# OK1050-C_V1_2_Lcd.net
KiCad netlist of a schematic drawn in Altium Designer
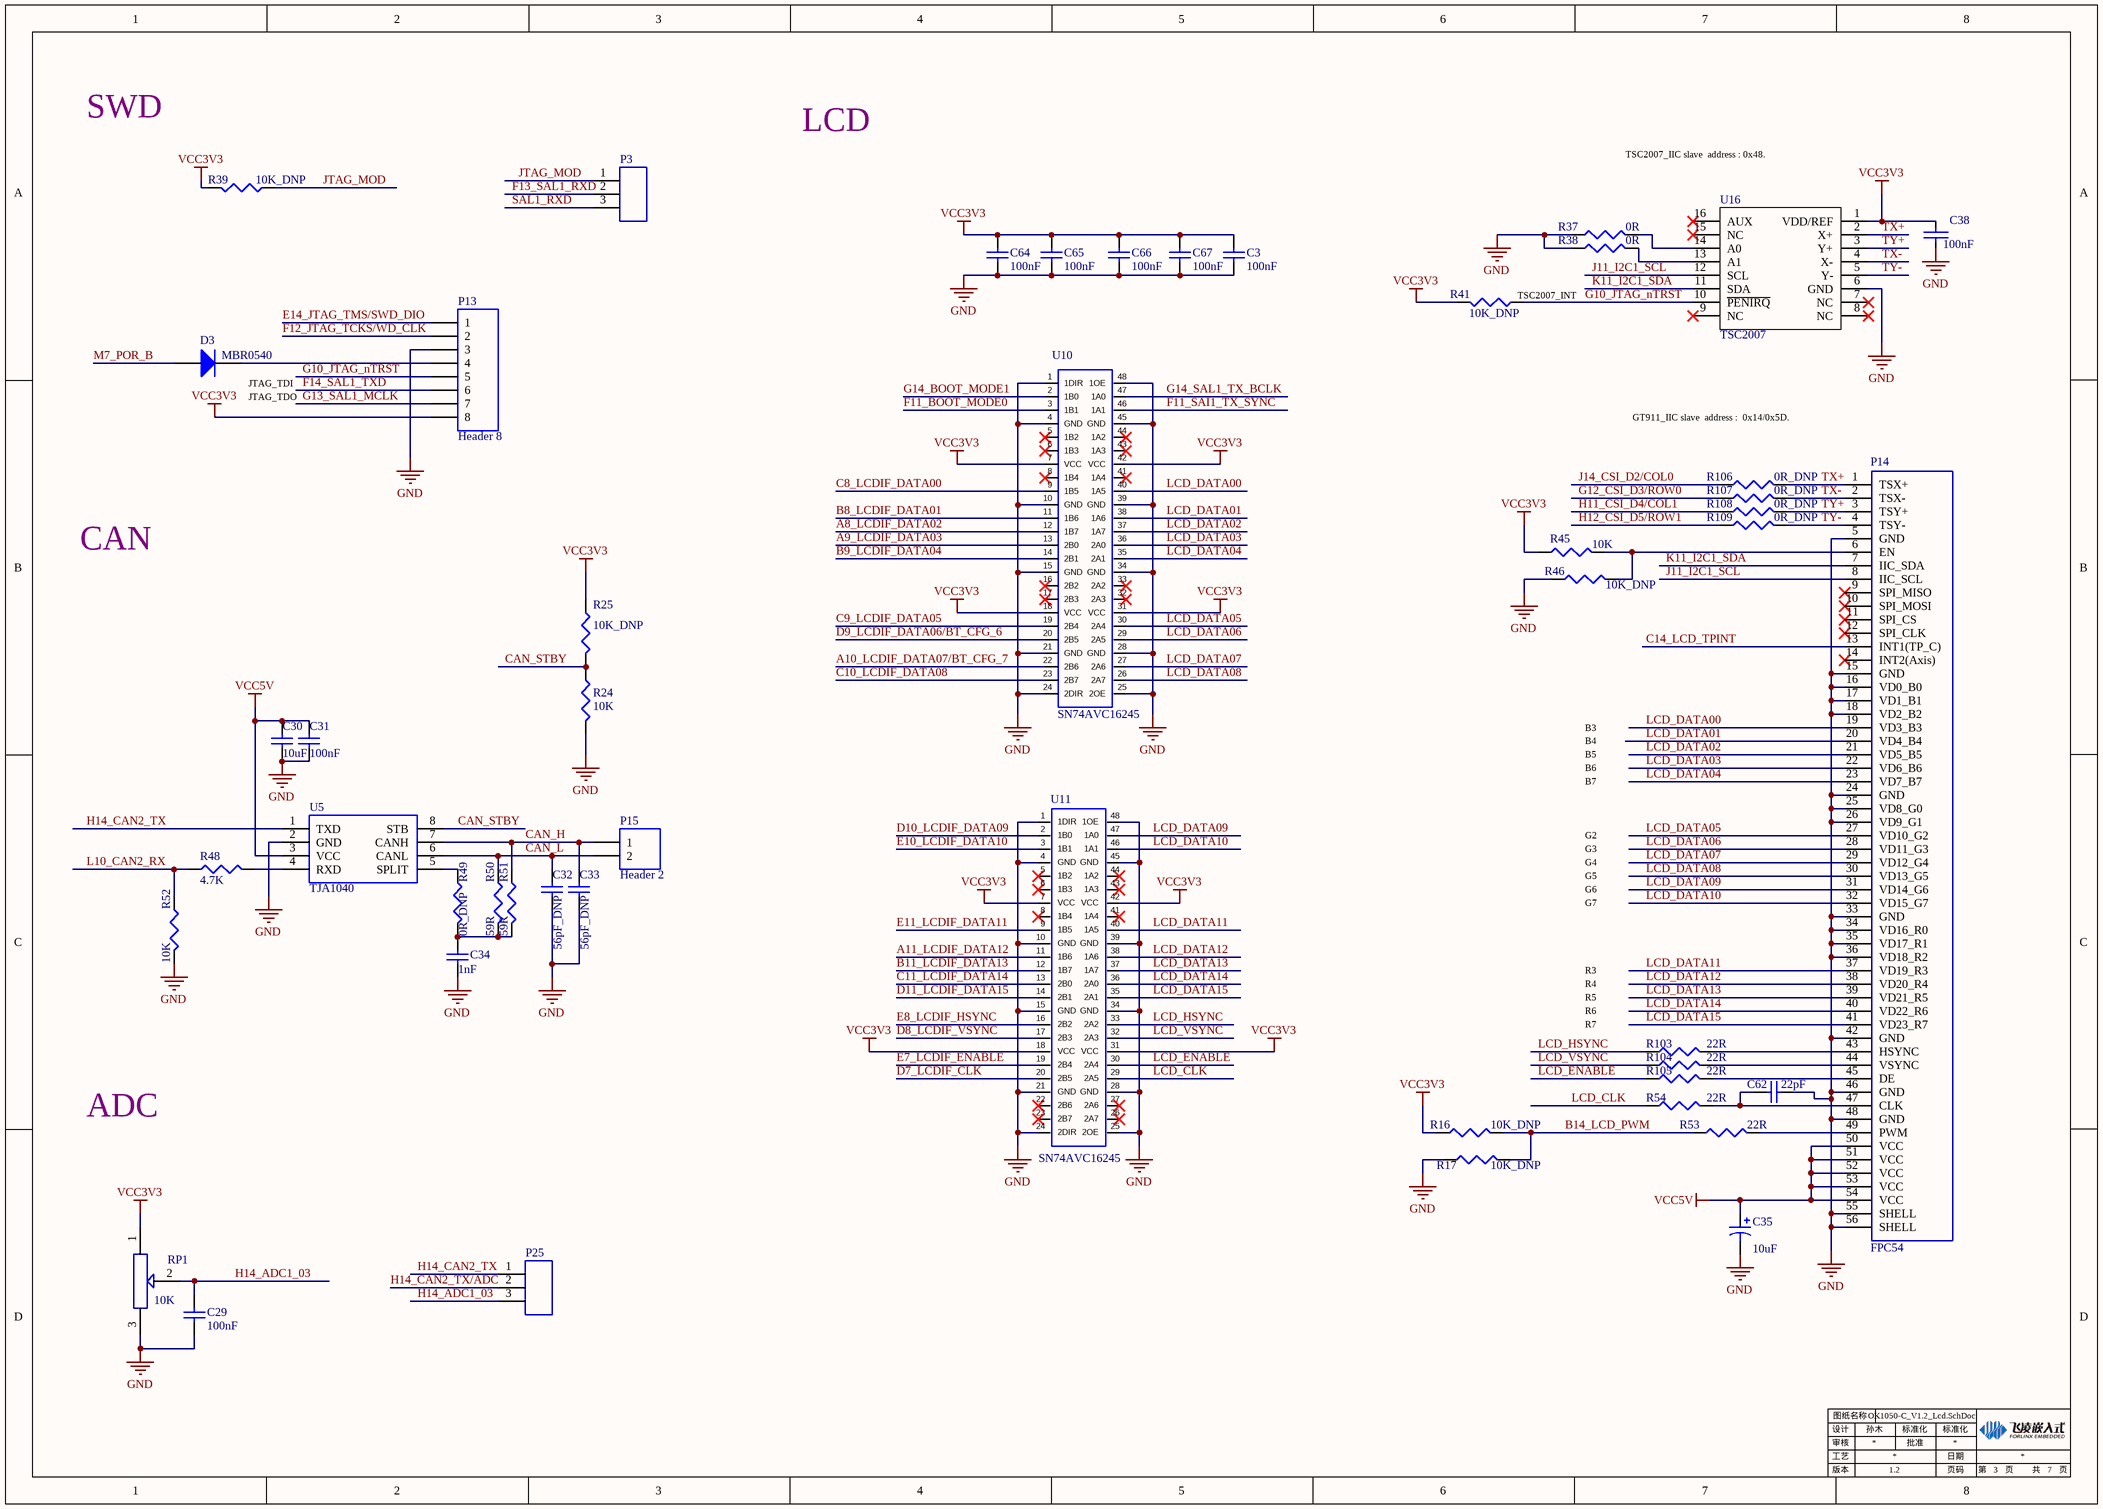
[diagram p0: OK1050-C_V1.2_Lcd.SchDoc]

(export (version "E")
  (design (tool "Eeschema 10.0.6"))
  (components
    (comp (ref "C3")
      (value "100nF")
      (footprint "0603C+")
      (description "Capacitor")
      (fields (field (name "PUBLISHER") "Altium Limited"))
      (libsource (lib "Miscellaneous Devices") (part "Cap"))
    )
    (comp (ref "C29")
      (value "100nF")
      (footprint "0603C+")
      (description "Capacitor")
      (fields (field (name "PUBLISHER") "Altium Limited"))
      (libsource (lib "Miscellaneous Devices") (part "Cap"))
    )
    (comp (ref "C30")
      (value "10uF")
      (footprint "0603C+")
      (description "Capacitor")
      (fields (field (name "PUBLISHER") "Altium Limited"))
      (libsource (lib "Miscellaneous Devices") (part "Cap"))
    )
    (comp (ref "C31")
      (value "100nF")
      (footprint "0603C+")
      (description "Capacitor")
      (fields (field (name "PUBLISHER") "Altium Limited"))
      (libsource (lib "Miscellaneous Devices") (part "Cap"))
    )
    (comp (ref "C32")
      (value "56pF_DNP")
      (footprint "0603C+")
      (description "Capacitor")
      (fields (field (name "PUBLISHER") "Altium Limited"))
      (libsource (lib "Miscellaneous Devices") (part "Cap"))
    )
    (comp (ref "C33")
      (value "56pF_DNP")
      (footprint "0603C+")
      (description "Capacitor")
      (fields (field (name "PUBLISHER") "Altium Limited"))
      (libsource (lib "Miscellaneous Devices") (part "Cap"))
    )
    (comp (ref "C34")
      (value "1nF")
      (footprint "0603C+")
      (description "Capacitor")
      (fields (field (name "PUBLISHER") "Altium Limited"))
      (libsource (lib "Miscellaneous Devices") (part "Cap"))
    )
    (comp (ref "C35")
      (value "10uF")
      (footprint "TC3216A")
      (description "Polarized Capacitor (Radial)")
      (fields (field (name "PUBLISHER") "Altium Limited"))
      (libsource (lib "Miscellaneous Devices") (part "Cap Pol1"))
    )
    (comp (ref "C38")
      (value "100nF")
      (footprint "0603C+")
      (libsource (lib "SMARTCORTEX M3-1700_1") (part "CAP_1"))
    )
    (comp (ref "C62")
      (value "22pF")
      (footprint "0603C+")
      (description "Capacitor")
      (fields (field (name "PUBLISHER") "Altium Limited"))
      (libsource (lib "Miscellaneous Devices") (part "Cap"))
    )
    (comp (ref "C64")
      (value "100nF")
      (footprint "0603C+")
      (description "Capacitor")
      (fields (field (name "PUBLISHER") "Altium Limited"))
      (libsource (lib "Miscellaneous Devices") (part "Cap"))
    )
    (comp (ref "C65")
      (value "100nF")
      (footprint "0603C+")
      (description "Capacitor")
      (fields (field (name "PUBLISHER") "Altium Limited"))
      (libsource (lib "Miscellaneous Devices") (part "Cap"))
    )
    (comp (ref "C66")
      (value "100nF")
      (footprint "0603C+")
      (description "Capacitor")
      (fields (field (name "PUBLISHER") "Altium Limited"))
      (libsource (lib "Miscellaneous Devices") (part "Cap"))
    )
    (comp (ref "C67")
      (value "100nF")
      (footprint "0603C+")
      (description "Capacitor")
      (fields (field (name "PUBLISHER") "Altium Limited"))
      (libsource (lib "Miscellaneous Devices") (part "Cap"))
    )
    (comp (ref "D3")
      (value "MBR0540")
      (footprint "Diode1.6*2.6")
      (description "Default Diode")
      (fields (field (name "PUBLISHER") "Altium Limited"))
      (libsource (lib "Miscellaneous Devices") (part "Diode"))
    )
    (comp (ref "P3") (value "P25") (footprint "HDR1X3") (libsource (lib "PCB_RT1052") (part "CON3")))
    (comp (ref "P13")
      (value "Header 8")
      (footprint "HDR1X8")
      (description "Header, 8-Pin")
      (fields (field (name "PUBLISHER") "Altium Limited"))
      (libsource (lib "PCB_RT1052_1") (part "Header 8"))
    )
    (comp (ref "P14") (value "FPC54") (footprint "FPC54") (libsource (lib "MyLIB") (part "FPC54")))
    (comp (ref "P15")
      (value "Header 2")
      (footprint "DG128-2P")
      (libsource (lib "PCB_RT1052") (part "Header 2"))
    )
    (comp (ref "P25") (value "P25") (footprint "HDR1X3") (libsource (lib "PCB_RT1052") (part "CON3")))
    (comp (ref "R16")
      (value "10K_DNP")
      (footprint "0603R+")
      (description "Resistor")
      (fields (field (name "PUBLISHER") "Altium Limited"))
      (libsource (lib "") (part "Res3_1"))
    )
    (comp (ref "R17")
      (value "10K_DNP")
      (footprint "0603R+")
      (description "Resistor")
      (fields (field (name "PUBLISHER") "Altium Limited"))
      (libsource (lib "") (part "Res3_1"))
    )
    (comp (ref "R24")
      (value "10K")
      (footprint "0603R+")
      (description "Resistor")
      (fields (field (name "PUBLISHER") "Altium Limited"))
      (libsource (lib "Miscellaneous Devices") (part "Res3"))
    )
    (comp (ref "R25")
      (value "10K_DNP")
      (footprint "0603R+")
      (description "Resistor")
      (fields (field (name "PUBLISHER") "Altium Limited"))
      (libsource (lib "Miscellaneous Devices") (part "Res3"))
    )
    (comp (ref "R37")
      (value "0R")
      (footprint "0603R+")
      (description "Resistor")
      (fields (field (name "PUBLISHER") "Altium Limited"))
      (libsource (lib "Sch") (part "Res3"))
    )
    (comp (ref "R38")
      (value "0R")
      (footprint "0603R+")
      (description "Resistor")
      (fields (field (name "PUBLISHER") "Altium Limited"))
      (libsource (lib "Sch") (part "Res3"))
    )
    (comp (ref "R39")
      (value "10K_DNP")
      (footprint "0603R+")
      (description "Resistor")
      (fields (field (name "PUBLISHER") "Altium Limited"))
      (libsource (lib "") (part "Res3_1"))
    )
    (comp (ref "R41")
      (value "10K_DNP")
      (footprint "0603R+")
      (description "Resistor")
      (fields (field (name "PUBLISHER") "Altium Limited"))
      (libsource (lib "Sch") (part "Res3"))
    )
    (comp (ref "R45")
      (value "10K")
      (footprint "0603R+")
      (description "Resistor")
      (fields (field (name "PUBLISHER") "Altium Limited"))
      (libsource (lib "") (part "Res3_1"))
    )
    (comp (ref "R46")
      (value "10K_DNP")
      (footprint "0603R+")
      (description "Resistor")
      (fields (field (name "PUBLISHER") "Altium Limited"))
      (libsource (lib "") (part "Res3_1"))
    )
    (comp (ref "R48")
      (value "4.7K")
      (footprint "0603R+")
      (description "Resistor")
      (fields (field (name "PUBLISHER") "Altium Limited"))
      (libsource (lib "Miscellaneous Devices") (part "Res3"))
    )
    (comp (ref "R49")
      (value "0R_DNP")
      (footprint "0603R+")
      (description "Resistor")
      (fields (field (name "PUBLISHER") "Altium Limited"))
      (libsource (lib "Miscellaneous Devices") (part "Res3"))
    )
    (comp (ref "R50")
      (value "59R")
      (footprint "0603R+")
      (description "Resistor")
      (fields (field (name "PUBLISHER") "Altium Limited"))
      (libsource (lib "Miscellaneous Devices") (part "Res3"))
    )
    (comp (ref "R51")
      (value "59R")
      (footprint "0603R+")
      (description "Resistor")
      (fields (field (name "PUBLISHER") "Altium Limited"))
      (libsource (lib "Miscellaneous Devices") (part "Res3"))
    )
    (comp (ref "R52")
      (value "10K")
      (footprint "0603R+")
      (description "Resistor")
      (fields (field (name "PUBLISHER") "Altium Limited"))
      (libsource (lib "Miscellaneous Devices") (part "Res3"))
    )
    (comp (ref "R53")
      (value "22R")
      (footprint "0603R+")
      (description "Resistor")
      (fields (field (name "PUBLISHER") "Altium Limited"))
      (libsource (lib "") (part "Res3_1"))
    )
    (comp (ref "R54")
      (value "22R")
      (footprint "0603R+")
      (description "Resistor")
      (fields (field (name "PUBLISHER") "Altium Limited"))
      (libsource (lib "") (part "Res3_1"))
    )
    (comp (ref "R103")
      (value "22R")
      (footprint "0603R+")
      (description "Resistor")
      (fields (field (name "PUBLISHER") "Altium Limited"))
      (libsource (lib "") (part "Res3_1"))
    )
    (comp (ref "R104")
      (value "22R")
      (footprint "0603R+")
      (description "Resistor")
      (fields (field (name "PUBLISHER") "Altium Limited"))
      (libsource (lib "") (part "Res3_1"))
    )
    (comp (ref "R105")
      (value "22R")
      (footprint "0603R+")
      (description "Resistor")
      (fields (field (name "PUBLISHER") "Altium Limited"))
      (libsource (lib "") (part "Res3_1"))
    )
    (comp (ref "R106")
      (value "0R_DNP")
      (footprint "0603R+")
      (description "Resistor")
      (fields (field (name "PUBLISHER") "Altium Limited"))
      (libsource (lib "Sch") (part "Res3"))
    )
    (comp (ref "R107")
      (value "0R_DNP")
      (footprint "0603R+")
      (description "Resistor")
      (fields (field (name "PUBLISHER") "Altium Limited"))
      (libsource (lib "Sch") (part "Res3"))
    )
    (comp (ref "R108")
      (value "0R_DNP")
      (footprint "0603R+")
      (description "Resistor")
      (fields (field (name "PUBLISHER") "Altium Limited"))
      (libsource (lib "Sch") (part "Res3"))
    )
    (comp (ref "R109")
      (value "0R_DNP")
      (footprint "0603R+")
      (description "Resistor")
      (fields (field (name "PUBLISHER") "Altium Limited"))
      (libsource (lib "Sch") (part "Res3"))
    )
    (comp (ref "RP1")
      (value "10K")
      (footprint "3296W")
      (fields (field (name "Comment") "VR-3296W"))
      (libsource (lib "Sch") (part "VR"))
    )
    (comp (ref "U5")
      (value "TJA1040")
      (footprint "SOP127P600X175-8N")
      (libsource (lib "IMX6QP") (part "TJA1040"))
    )
    (comp (ref "U10")
      (value "SN74AVC16245")
      (footprint "SN74VC16245")
      (libsource (lib "MyLIB") (part "SN74AVC16245"))
    )
    (comp (ref "U11")
      (value "SN74AVC16245")
      (footprint "SN74VC16245")
      (libsource (lib "MyLIB") (part "SN74AVC16245"))
    )
    (comp (ref "U16") (value "TSC2007") (footprint "TSC2007") (libsource (lib "IMX6Q-S3") (part "TSC2007")))
  )
  (nets
    (net (code "1") (name "/A8_LCDIF_DATA02") (class "Default")
      (node (ref "U10") (pin "12") (pinfunction "1B7_12") (pintype "passive"))
    )
    (net (code "2") (name "/A9_LCDIF_DATA03") (class "Default")
      (node (ref "U10") (pin "13") (pinfunction "2B0_13") (pintype "passive"))
    )
    (net (code "3") (name "/A10_LCDIF_DATA07{slash}BT_CFG_7") (class "Default")
      (node (ref "U10") (pin "22") (pinfunction "2B6_22") (pintype "passive"))
    )
    (net (code "4") (name "/A11_LCDIF_DATA12") (class "Default")
      (node (ref "U11") (pin "11") (pinfunction "1B6_11") (pintype "passive"))
    )
    (net (code "5") (name "/B8_LCDIF_DATA01") (class "Default")
      (node (ref "U10") (pin "11") (pinfunction "1B6_11") (pintype "passive"))
    )
    (net (code "6") (name "/B9_LCDIF_DATA04") (class "Default")
      (node (ref "U10") (pin "14") (pinfunction "2B1_14") (pintype "passive"))
    )
    (net (code "7") (name "/B11_LCDIF_DATA13") (class "Default")
      (node (ref "U11") (pin "12") (pinfunction "1B7_12") (pintype "passive"))
    )
    (net (code "8") (name "/B14_LCD_PWM") (class "Default")
      (node (ref "R16") (pin "2") (pinfunction "2_2") (pintype "passive"))
      (node (ref "R17") (pin "2") (pinfunction "2_2") (pintype "passive"))
      (node (ref "R53") (pin "1") (pinfunction "1_1") (pintype "passive"))
    )
    (net (code "9") (name "/C8_LCDIF_DATA00") (class "Default")
      (node (ref "U10") (pin "9") (pinfunction "1B5_9") (pintype "passive"))
    )
    (net (code "10") (name "/C9_LCDIF_DATA05") (class "Default")
      (node (ref "U10") (pin "19") (pinfunction "2B4_19") (pintype "passive"))
    )
    (net (code "11") (name "/C10_LCDIF_DATA08") (class "Default")
      (node (ref "U10") (pin "23") (pinfunction "2B7_23") (pintype "passive"))
    )
    (net (code "12") (name "/C11_LCDIF_DATA14") (class "Default")
      (node (ref "U11") (pin "13") (pinfunction "2B0_13") (pintype "passive"))
    )
    (net (code "13") (name "/C14_LCD_TPINT") (class "Default")
      (node (ref "P14") (pin "13") (pinfunction "INT1(TP_C)_13") (pintype "passive"))
    )
    (net (code "14") (name "/CAN_H") (class "Default")
      (node (ref "C33") (pin "1") (pinfunction "1_1") (pintype "passive"))
      (node (ref "P15") (pin "1") (pinfunction "1_1") (pintype "passive"))
      (node (ref "R51") (pin "1") (pinfunction "1_1") (pintype "passive"))
      (node (ref "U5") (pin "7") (pinfunction "CANH_7") (pintype "passive"))
    )
    (net (code "15") (name "/CAN_L") (class "Default")
      (node (ref "C32") (pin "1") (pinfunction "1_1") (pintype "passive"))
      (node (ref "P15") (pin "2") (pinfunction "2_2") (pintype "passive"))
      (node (ref "R50") (pin "1") (pinfunction "1_1") (pintype "passive"))
      (node (ref "U5") (pin "6") (pinfunction "CANL_6") (pintype "passive"))
    )
    (net (code "16") (name "/CAN_STBY") (class "Default")
      (node (ref "R24") (pin "1") (pinfunction "1_1") (pintype "passive"))
      (node (ref "R25") (pin "2") (pinfunction "2_2") (pintype "passive"))
      (node (ref "U5") (pin "8") (pinfunction "STB_8") (pintype "passive"))
    )
    (net (code "17") (name "/D7_LCDIF_CLK") (class "Default")
      (node (ref "U11") (pin "20") (pinfunction "2B5_20") (pintype "passive"))
    )
    (net (code "18") (name "/D8_LCDIF_VSYNC") (class "Default")
      (node (ref "U11") (pin "17") (pinfunction "2B3_17") (pintype "passive"))
    )
    (net (code "19") (name "/D9_LCDIF_DATA06{slash}BT_CFG_6") (class "Default")
      (node (ref "U10") (pin "20") (pinfunction "2B5_20") (pintype "passive"))
    )
    (net (code "20") (name "/D10_LCDIF_DATA09") (class "Default")
      (node (ref "U11") (pin "2") (pinfunction "1B0_2") (pintype "passive"))
    )
    (net (code "21") (name "/D11_LCDIF_DATA15") (class "Default")
      (node (ref "U11") (pin "14") (pinfunction "2B1_14") (pintype "passive"))
    )
    (net (code "22") (name "/E7_LCDIF_ENABLE") (class "Default")
      (node (ref "U11") (pin "19") (pinfunction "2B4_19") (pintype "passive"))
    )
    (net (code "23") (name "/E8_LCDIF_HSYNC") (class "Default")
      (node (ref "U11") (pin "16") (pinfunction "2B2_16") (pintype "passive"))
    )
    (net (code "24") (name "/E10_LCDIF_DATA10") (class "Default")
      (node (ref "U11") (pin "3") (pinfunction "1B1_3") (pintype "passive"))
    )
    (net (code "25") (name "/E11_LCDIF_DATA11") (class "Default")
      (node (ref "U11") (pin "9") (pinfunction "1B5_9") (pintype "passive"))
    )
    (net (code "26") (name "/E14_JTAG_TMS{slash}SWD_DIO") (class "Default")
      (node (ref "P13") (pin "1") (pinfunction "1_1") (pintype "passive"))
    )
    (net (code "27") (name "/F11_BOOT_MODE0") (class "Default")
      (node (ref "U10") (pin "3") (pinfunction "1B1_3") (pintype "passive"))
    )
    (net (code "28") (name "/F11_SAI1_TX_SYNC") (class "Default")
      (node (ref "U10") (pin "46") (pinfunction "1A1_46") (pintype "passive"))
    )
    (net (code "29") (name "/F12_JTAG_TCKS{slash}WD_CLK") (class "Default")
      (node (ref "P13") (pin "2") (pinfunction "2_2") (pintype "passive"))
    )
    (net (code "30") (name "/F13_SAL1_RXD") (class "Default")
      (node (ref "P3") (pin "2") (pinfunction "DQ17_2") (pintype "passive"))
    )
    (net (code "31") (name "/F14_SAL1_TXD") (class "Default")
      (node (ref "P13") (pin "6") (pinfunction "6_6") (pintype "passive"))
    )
    (net (code "32") (name "/G10_JTAG_nTRST") (class "Default")
      (node (ref "P13") (pin "5") (pinfunction "5_5") (pintype "passive"))
      (node (ref "R41") (pin "1") (pinfunction "1_1") (pintype "passive"))
      (node (ref "U16") (pin "10") (pinfunction "~{PENIRQ}_10") (pintype "passive"))
    )
    (net (code "33") (name "/G12_CSI_D3{slash}ROW0") (class "Default")
      (node (ref "R107") (pin "1") (pinfunction "1_1") (pintype "passive"))
    )
    (net (code "34") (name "/G13_SAL1_MCLK") (class "Default")
      (node (ref "P13") (pin "7") (pinfunction "7_7") (pintype "passive"))
    )
    (net (code "35") (name "/G14_BOOT_MODE1") (class "Default")
      (node (ref "U10") (pin "2") (pinfunction "1B0_2") (pintype "passive"))
    )
    (net (code "36") (name "/G14_SAL1_TX_BCLK") (class "Default")
      (node (ref "U10") (pin "47") (pinfunction "1A0_47") (pintype "passive"))
    )
    (net (code "37") (name "/H11_CSI_D4{slash}COL1") (class "Default")
      (node (ref "R108") (pin "1") (pinfunction "1_1") (pintype "passive"))
    )
    (net (code "38") (name "/H12_CSI_D5{slash}ROW1") (class "Default")
      (node (ref "R109") (pin "1") (pinfunction "1_1") (pintype "passive"))
    )
    (net (code "39") (name "/H14_ADC1_03") (class "Default")
      (node (ref "C29") (pin "2") (pinfunction "2_2") (pintype "passive"))
      (node (ref "P25") (pin "3") (pinfunction "DQ18_3") (pintype "passive"))
      (node (ref "RP1") (pin "2") (pinfunction "VCC_2") (pintype "passive"))
    )
    (net (code "40") (name "/H14_CAN2_TX") (class "Default")
      (node (ref "P25") (pin "1") (pinfunction "DQ16_1") (pintype "passive"))
      (node (ref "U5") (pin "1") (pinfunction "TXD_1") (pintype "passive"))
    )
    (net (code "41") (name "/H14_CAN2_TX{slash}ADC") (class "Default")
      (node (ref "P25") (pin "2") (pinfunction "DQ17_2") (pintype "passive"))
    )
    (net (code "42") (name "/J11_I2C1_SCL") (class "Default")
      (node (ref "P14") (pin "8") (pinfunction "IIC_SCL_8") (pintype "passive"))
      (node (ref "U16") (pin "12") (pinfunction "SCL_12") (pintype "passive"))
    )
    (net (code "43") (name "/J14_CSI_D2{slash}COL0") (class "Default")
      (node (ref "R106") (pin "1") (pinfunction "1_1") (pintype "passive"))
    )
    (net (code "44") (name "/JTAG_MOD") (class "Default")
      (node (ref "P3") (pin "1") (pinfunction "DQ16_1") (pintype "passive"))
      (node (ref "R39") (pin "1") (pinfunction "1_1") (pintype "passive"))
    )
    (net (code "45") (name "/K11_I2C1_SDA") (class "Default")
      (node (ref "P14") (pin "7") (pinfunction "IIC_SDA_7") (pintype "passive"))
      (node (ref "U16") (pin "11") (pinfunction "SDA_11") (pintype "passive"))
    )
    (net (code "46") (name "/L10_CAN2_RX") (class "Default")
      (node (ref "R48") (pin "1") (pinfunction "1_1") (pintype "passive"))
      (node (ref "R52") (pin "1") (pinfunction "1_1") (pintype "passive"))
    )
    (net (code "47") (name "/LCD_CLK") (class "Default")
      (node (ref "R54") (pin "1") (pinfunction "1_1") (pintype "passive"))
      (node (ref "U11") (pin "29") (pinfunction "2A5_29") (pintype "passive"))
    )
    (net (code "48") (name "/LCD_DATA00") (class "Default")
      (node (ref "P14") (pin "19") (pinfunction "VD3_B3_19") (pintype "passive"))
      (node (ref "U10") (pin "40") (pinfunction "1A5_40") (pintype "passive"))
    )
    (net (code "49") (name "/LCD_DATA01") (class "Default")
      (node (ref "P14") (pin "20") (pinfunction "VD4_B4_20") (pintype "passive"))
      (node (ref "U10") (pin "38") (pinfunction "1A6_38") (pintype "passive"))
    )
    (net (code "50") (name "/LCD_DATA02") (class "Default")
      (node (ref "P14") (pin "21") (pinfunction "VD5_B5_21") (pintype "passive"))
      (node (ref "U10") (pin "37") (pinfunction "1A7_37") (pintype "passive"))
    )
    (net (code "51") (name "/LCD_DATA03") (class "Default")
      (node (ref "P14") (pin "22") (pinfunction "VD6_B6_22") (pintype "passive"))
      (node (ref "U10") (pin "36") (pinfunction "2A0_36") (pintype "passive"))
    )
    (net (code "52") (name "/LCD_DATA04") (class "Default")
      (node (ref "P14") (pin "23") (pinfunction "VD7_B7_23") (pintype "passive"))
      (node (ref "U10") (pin "35") (pinfunction "2A1_35") (pintype "passive"))
    )
    (net (code "53") (name "/LCD_DATA05") (class "Default")
      (node (ref "P14") (pin "27") (pinfunction "VD10_G2_27") (pintype "passive"))
      (node (ref "U10") (pin "30") (pinfunction "2A4_30") (pintype "passive"))
    )
    (net (code "54") (name "/LCD_DATA06") (class "Default")
      (node (ref "P14") (pin "28") (pinfunction "VD11_G3_28") (pintype "passive"))
      (node (ref "U10") (pin "29") (pinfunction "2A5_29") (pintype "passive"))
    )
    (net (code "55") (name "/LCD_DATA07") (class "Default")
      (node (ref "P14") (pin "29") (pinfunction "VD12_G4_29") (pintype "passive"))
      (node (ref "U10") (pin "27") (pinfunction "2A6_27") (pintype "passive"))
    )
    (net (code "56") (name "/LCD_DATA08") (class "Default")
      (node (ref "P14") (pin "30") (pinfunction "VD13_G5_30") (pintype "passive"))
      (node (ref "U10") (pin "26") (pinfunction "2A7_26") (pintype "passive"))
    )
    (net (code "57") (name "/LCD_DATA09") (class "Default")
      (node (ref "P14") (pin "31") (pinfunction "VD14_G6_31") (pintype "passive"))
      (node (ref "U11") (pin "47") (pinfunction "1A0_47") (pintype "passive"))
    )
    (net (code "58") (name "/LCD_DATA10") (class "Default")
      (node (ref "P14") (pin "32") (pinfunction "VD15_G7_32") (pintype "passive"))
      (node (ref "U11") (pin "46") (pinfunction "1A1_46") (pintype "passive"))
    )
    (net (code "59") (name "/LCD_DATA11") (class "Default")
      (node (ref "P14") (pin "37") (pinfunction "VD19_R3_37") (pintype "passive"))
      (node (ref "U11") (pin "40") (pinfunction "1A5_40") (pintype "passive"))
    )
    (net (code "60") (name "/LCD_DATA12") (class "Default")
      (node (ref "P14") (pin "38") (pinfunction "VD20_R4_38") (pintype "passive"))
      (node (ref "U11") (pin "38") (pinfunction "1A6_38") (pintype "passive"))
    )
    (net (code "61") (name "/LCD_DATA13") (class "Default")
      (node (ref "P14") (pin "39") (pinfunction "VD21_R5_39") (pintype "passive"))
      (node (ref "U11") (pin "37") (pinfunction "1A7_37") (pintype "passive"))
    )
    (net (code "62") (name "/LCD_DATA14") (class "Default")
      (node (ref "P14") (pin "40") (pinfunction "VD22_R6_40") (pintype "passive"))
      (node (ref "U11") (pin "36") (pinfunction "2A0_36") (pintype "passive"))
    )
    (net (code "63") (name "/LCD_DATA15") (class "Default")
      (node (ref "P14") (pin "41") (pinfunction "VD23_R7_41") (pintype "passive"))
      (node (ref "U11") (pin "35") (pinfunction "2A1_35") (pintype "passive"))
    )
    (net (code "64") (name "/LCD_ENABLE") (class "Default")
      (node (ref "R105") (pin "1") (pinfunction "1_1") (pintype "passive"))
      (node (ref "U11") (pin "30") (pinfunction "2A4_30") (pintype "passive"))
    )
    (net (code "65") (name "/LCD_HSYNC") (class "Default")
      (node (ref "R103") (pin "1") (pinfunction "1_1") (pintype "passive"))
      (node (ref "U11") (pin "33") (pinfunction "2A2_33") (pintype "passive"))
    )
    (net (code "66") (name "/LCD_VSYNC") (class "Default")
      (node (ref "R104") (pin "1") (pinfunction "1_1") (pintype "passive"))
      (node (ref "U11") (pin "32") (pinfunction "2A3_32") (pintype "passive"))
    )
    (net (code "67") (name "/M7_POR_B") (class "Default")
      (node (ref "D3") (pin "1") (pinfunction "A_1") (pintype "passive"))
    )
    (net (code "68") (name "/SAL1_RXD") (class "Default")
      (node (ref "P3") (pin "3") (pinfunction "DQ18_3") (pintype "passive"))
    )
    (net (code "69") (name "/TX+") (class "Default")
      (node (ref "P14") (pin "1") (pinfunction "TSX+_1") (pintype "passive"))
      (node (ref "R106") (pin "2") (pinfunction "2_2") (pintype "passive"))
      (node (ref "U16") (pin "2") (pinfunction "X+_2") (pintype "passive"))
    )
    (net (code "70") (name "/TX-") (class "Default")
      (node (ref "P14") (pin "2") (pinfunction "TSX-_2") (pintype "passive"))
      (node (ref "R107") (pin "2") (pinfunction "2_2") (pintype "passive"))
      (node (ref "U16") (pin "4") (pinfunction "X-_4") (pintype "passive"))
    )
    (net (code "71") (name "/TY+") (class "Default")
      (node (ref "P14") (pin "3") (pinfunction "TSY+_3") (pintype "passive"))
      (node (ref "R108") (pin "2") (pinfunction "2_2") (pintype "passive"))
      (node (ref "U16") (pin "3") (pinfunction "Y+_3") (pintype "passive"))
    )
    (net (code "72") (name "/TY-") (class "Default")
      (node (ref "P14") (pin "4") (pinfunction "TSY-_4") (pintype "passive"))
      (node (ref "R109") (pin "2") (pinfunction "2_2") (pintype "passive"))
      (node (ref "U16") (pin "5") (pinfunction "Y-_5") (pintype "passive"))
    )
    (net (code "73") (name "GND") (class "Default")
      (node (ref "C29") (pin "1") (pinfunction "1_1") (pintype "passive"))
      (node (ref "C3") (pin "1") (pinfunction "1_1") (pintype "passive"))
      (node (ref "C30") (pin "2") (pinfunction "2_2") (pintype "passive"))
      (node (ref "C31") (pin "2") (pinfunction "2_2") (pintype "passive"))
      (node (ref "C32") (pin "2") (pinfunction "2_2") (pintype "passive"))
      (node (ref "C33") (pin "2") (pinfunction "2_2") (pintype "passive"))
      (node (ref "C34") (pin "2") (pinfunction "2_2") (pintype "passive"))
      (node (ref "C35") (pin "2") (pinfunction "2_2") (pintype "passive"))
      (node (ref "C38") (pin "2") (pintype "passive"))
      (node (ref "C62") (pin "2") (pinfunction "2_2") (pintype "passive"))
      (node (ref "C64") (pin "1") (pinfunction "1_1") (pintype "passive"))
      (node (ref "C65") (pin "1") (pinfunction "1_1") (pintype "passive"))
      (node (ref "C66") (pin "1") (pinfunction "1_1") (pintype "passive"))
      (node (ref "C67") (pin "1") (pinfunction "1_1") (pintype "passive"))
      (node (ref "P13") (pin "3") (pinfunction "3_3") (pintype "passive"))
      (node (ref "P14") (pin "15") (pinfunction "GND_15") (pintype "passive"))
      (node (ref "P14") (pin "16") (pinfunction "VD0_B0_16") (pintype "passive"))
      (node (ref "P14") (pin "17") (pinfunction "VD1_B1_17") (pintype "passive"))
      (node (ref "P14") (pin "18") (pinfunction "VD2_B2_18") (pintype "passive"))
      (node (ref "P14") (pin "24") (pinfunction "GND_24") (pintype "passive"))
      (node (ref "P14") (pin "25") (pinfunction "VD8_G0_25") (pintype "passive"))
      (node (ref "P14") (pin "26") (pinfunction "VD9_G1_26") (pintype "passive"))
      (node (ref "P14") (pin "33") (pinfunction "GND_33") (pintype "passive"))
      (node (ref "P14") (pin "34") (pinfunction "VD16_R0_34") (pintype "passive"))
      (node (ref "P14") (pin "35") (pinfunction "VD17_R1_35") (pintype "passive"))
      (node (ref "P14") (pin "36") (pinfunction "VD18_R2_36") (pintype "passive"))
      (node (ref "P14") (pin "42") (pinfunction "GND_42") (pintype "passive"))
      (node (ref "P14") (pin "46") (pinfunction "GND_46") (pintype "passive"))
      (node (ref "P14") (pin "48") (pinfunction "GND_48") (pintype "passive"))
      (node (ref "P14") (pin "5") (pinfunction "GND_5") (pintype "passive"))
      (node (ref "P14") (pin "55") (pinfunction "SHELL_55") (pintype "passive"))
      (node (ref "P14") (pin "56") (pinfunction "SHELL_56") (pintype "passive"))
      (node (ref "R17") (pin "1") (pinfunction "1_1") (pintype "passive"))
      (node (ref "R24") (pin "2") (pinfunction "2_2") (pintype "passive"))
      (node (ref "R37") (pin "1") (pinfunction "1_1") (pintype "passive"))
      (node (ref "R38") (pin "1") (pinfunction "1_1") (pintype "passive"))
      (node (ref "R46") (pin "1") (pinfunction "1_1") (pintype "passive"))
      (node (ref "R52") (pin "2") (pinfunction "2_2") (pintype "passive"))
      (node (ref "RP1") (pin "3") (pinfunction "VCC_3") (pintype "passive"))
      (node (ref "U10") (pin "1") (pinfunction "1DIR_1") (pintype "passive"))
      (node (ref "U10") (pin "10") (pinfunction "GND_10") (pintype "passive"))
      (node (ref "U10") (pin "15") (pinfunction "GND_15") (pintype "passive"))
      (node (ref "U10") (pin "21") (pinfunction "GND_21") (pintype "passive"))
      (node (ref "U10") (pin "24") (pinfunction "2DIR_24") (pintype "passive"))
      (node (ref "U10") (pin "25") (pinfunction "2OE_25") (pintype "passive"))
      (node (ref "U10") (pin "28") (pinfunction "GND_28") (pintype "passive"))
      (node (ref "U10") (pin "34") (pinfunction "GND_34") (pintype "passive"))
      (node (ref "U10") (pin "39") (pinfunction "GND_39") (pintype "passive"))
      (node (ref "U10") (pin "4") (pinfunction "GND_4") (pintype "passive"))
      (node (ref "U10") (pin "45") (pinfunction "GND_45") (pintype "passive"))
      (node (ref "U10") (pin "48") (pinfunction "1OE_48") (pintype "passive"))
      (node (ref "U11") (pin "1") (pinfunction "1DIR_1") (pintype "passive"))
      (node (ref "U11") (pin "10") (pinfunction "GND_10") (pintype "passive"))
      (node (ref "U11") (pin "15") (pinfunction "GND_15") (pintype "passive"))
      (node (ref "U11") (pin "21") (pinfunction "GND_21") (pintype "passive"))
      (node (ref "U11") (pin "24") (pinfunction "2DIR_24") (pintype "passive"))
      (node (ref "U11") (pin "25") (pinfunction "2OE_25") (pintype "passive"))
      (node (ref "U11") (pin "28") (pinfunction "GND_28") (pintype "passive"))
      (node (ref "U11") (pin "34") (pinfunction "GND_34") (pintype "passive"))
      (node (ref "U11") (pin "39") (pinfunction "GND_39") (pintype "passive"))
      (node (ref "U11") (pin "4") (pinfunction "GND_4") (pintype "passive"))
      (node (ref "U11") (pin "45") (pinfunction "GND_45") (pintype "passive"))
      (node (ref "U11") (pin "48") (pinfunction "1OE_48") (pintype "passive"))
      (node (ref "U16") (pin "6") (pinfunction "GND_6") (pintype "passive"))
      (node (ref "U5") (pin "2") (pinfunction "GND_2") (pintype "passive"))
    )
    (net (code "74") (name "Net-(C34-Pad1)") (class "Default")
      (node (ref "C34") (pin "1") (pinfunction "1_1") (pintype "passive"))
      (node (ref "R49") (pin "2") (pinfunction "2_2") (pintype "passive"))
      (node (ref "R50") (pin "2") (pinfunction "2_2") (pintype "passive"))
      (node (ref "R51") (pin "2") (pinfunction "2_2") (pintype "passive"))
    )
    (net (code "75") (name "Net-(D3-K)") (class "Default")
      (node (ref "D3") (pin "2") (pinfunction "K_2") (pintype "passive"))
      (node (ref "P13") (pin "4") (pinfunction "4_4") (pintype "passive"))
    )
    (net (code "76") (name "Net-(P14-CLK)") (class "Default")
      (node (ref "C62") (pin "1") (pinfunction "1_1") (pintype "passive"))
      (node (ref "P14") (pin "47") (pinfunction "CLK_47") (pintype "passive"))
      (node (ref "R54") (pin "2") (pinfunction "2_2") (pintype "passive"))
    )
    (net (code "77") (name "Net-(P14-DE)") (class "Default")
      (node (ref "P14") (pin "45") (pinfunction "DE_45") (pintype "passive"))
      (node (ref "R105") (pin "2") (pinfunction "2_2") (pintype "passive"))
    )
    (net (code "78") (name "Net-(P14-EN)") (class "Default")
      (node (ref "P14") (pin "6") (pinfunction "EN_6") (pintype "passive"))
      (node (ref "R45") (pin "2") (pinfunction "2_2") (pintype "passive"))
      (node (ref "R46") (pin "2") (pinfunction "2_2") (pintype "passive"))
    )
    (net (code "79") (name "Net-(P14-HSYNC)") (class "Default")
      (node (ref "P14") (pin "43") (pinfunction "HSYNC_43") (pintype "passive"))
      (node (ref "R103") (pin "2") (pinfunction "2_2") (pintype "passive"))
    )
    (net (code "80") (name "Net-(P14-PWM)") (class "Default")
      (node (ref "P14") (pin "49") (pinfunction "PWM_49") (pintype "passive"))
      (node (ref "R53") (pin "2") (pinfunction "2_2") (pintype "passive"))
    )
    (net (code "81") (name "Net-(P14-VSYNC)") (class "Default")
      (node (ref "P14") (pin "44") (pinfunction "VSYNC_44") (pintype "passive"))
      (node (ref "R104") (pin "2") (pinfunction "2_2") (pintype "passive"))
    )
    (net (code "82") (name "Net-(U5-RXD)") (class "Default")
      (node (ref "R48") (pin "2") (pinfunction "2_2") (pintype "passive"))
      (node (ref "U5") (pin "4") (pinfunction "RXD_4") (pintype "passive"))
    )
    (net (code "83") (name "Net-(U5-SPLIT)") (class "Default")
      (node (ref "R49") (pin "1") (pinfunction "1_1") (pintype "passive"))
      (node (ref "U5") (pin "5") (pinfunction "SPLIT_5") (pintype "passive"))
    )
    (net (code "84") (name "Net-(U16-A0)") (class "Default")
      (node (ref "R37") (pin "2") (pinfunction "2_2") (pintype "passive"))
      (node (ref "U16") (pin "14") (pinfunction "A0_14") (pintype "passive"))
    )
    (net (code "85") (name "Net-(U16-A1)") (class "Default")
      (node (ref "R38") (pin "2") (pinfunction "2_2") (pintype "passive"))
      (node (ref "U16") (pin "13") (pinfunction "A1_13") (pintype "passive"))
    )
    (net (code "86") (name "VCC3V3") (class "Default")
      (node (ref "C3") (pin "2") (pinfunction "2_2") (pintype "passive"))
      (node (ref "C38") (pin "1") (pintype "passive"))
      (node (ref "C64") (pin "2") (pinfunction "2_2") (pintype "passive"))
      (node (ref "C65") (pin "2") (pinfunction "2_2") (pintype "passive"))
      (node (ref "C66") (pin "2") (pinfunction "2_2") (pintype "passive"))
      (node (ref "C67") (pin "2") (pinfunction "2_2") (pintype "passive"))
      (node (ref "P13") (pin "8") (pinfunction "8_8") (pintype "passive"))
      (node (ref "R16") (pin "1") (pinfunction "1_1") (pintype "passive"))
      (node (ref "R25") (pin "1") (pinfunction "1_1") (pintype "passive"))
      (node (ref "R39") (pin "2") (pinfunction "2_2") (pintype "passive"))
      (node (ref "R41") (pin "2") (pinfunction "2_2") (pintype "passive"))
      (node (ref "R45") (pin "1") (pinfunction "1_1") (pintype "passive"))
      (node (ref "RP1") (pin "1") (pinfunction "VCC_1") (pintype "passive"))
      (node (ref "U10") (pin "18") (pinfunction "VCC_18") (pintype "passive"))
      (node (ref "U10") (pin "31") (pinfunction "VCC_31") (pintype "passive"))
      (node (ref "U10") (pin "42") (pinfunction "VCC_42") (pintype "passive"))
      (node (ref "U10") (pin "7") (pinfunction "VCC_7") (pintype "passive"))
      (node (ref "U11") (pin "18") (pinfunction "VCC_18") (pintype "passive"))
      (node (ref "U11") (pin "31") (pinfunction "VCC_31") (pintype "passive"))
      (node (ref "U11") (pin "42") (pinfunction "VCC_42") (pintype "passive"))
      (node (ref "U11") (pin "7") (pinfunction "VCC_7") (pintype "passive"))
      (node (ref "U16") (pin "1") (pinfunction "VDD/REF_1") (pintype "passive"))
    )
    (net (code "87") (name "VCC5V") (class "Default")
      (node (ref "C30") (pin "1") (pinfunction "1_1") (pintype "passive"))
      (node (ref "C31") (pin "1") (pinfunction "1_1") (pintype "passive"))
      (node (ref "C35") (pin "1") (pinfunction "1_1") (pintype "passive"))
      (node (ref "P14") (pin "50") (pinfunction "VCC_50") (pintype "passive"))
      (node (ref "P14") (pin "51") (pinfunction "VCC_51") (pintype "passive"))
      (node (ref "P14") (pin "52") (pinfunction "VCC_52") (pintype "passive"))
      (node (ref "P14") (pin "53") (pinfunction "VCC_53") (pintype "passive"))
      (node (ref "P14") (pin "54") (pinfunction "VCC_54") (pintype "passive"))
      (node (ref "U5") (pin "3") (pinfunction "VCC_3") (pintype "passive"))
    )
    (net (code "88") (name "unconnected-(P14-INT2(Axis)-Pad14)") (class "Default")
      (node (ref "P14") (pin "14") (pinfunction "INT2(Axis)_14") (pintype "passive+no_connect"))
    )
    (net (code "89") (name "unconnected-(P14-SPI_CLK-Pad12)") (class "Default")
      (node (ref "P14") (pin "12") (pinfunction "SPI_CLK_12") (pintype "passive+no_connect"))
    )
    (net (code "90") (name "unconnected-(P14-SPI_CS-Pad11)") (class "Default")
      (node (ref "P14") (pin "11") (pinfunction "SPI_CS_11") (pintype "passive+no_connect"))
    )
    (net (code "91") (name "unconnected-(P14-SPI_MISO-Pad9)") (class "Default")
      (node (ref "P14") (pin "9") (pinfunction "SPI_MISO_9") (pintype "passive+no_connect"))
    )
    (net (code "92") (name "unconnected-(P14-SPI_MOSI-Pad10)") (class "Default")
      (node (ref "P14") (pin "10") (pinfunction "SPI_MOSI_10") (pintype "passive+no_connect"))
    )
    (net (code "93") (name "unconnected-(U10-1A2-Pad44)") (class "Default")
      (node (ref "U10") (pin "44") (pinfunction "1A2_44") (pintype "passive+no_connect"))
    )
    (net (code "94") (name "unconnected-(U10-1A3-Pad43)") (class "Default")
      (node (ref "U10") (pin "43") (pinfunction "1A3_43") (pintype "passive+no_connect"))
    )
    (net (code "95") (name "unconnected-(U10-1A4-Pad41)") (class "Default")
      (node (ref "U10") (pin "41") (pinfunction "1A4_41") (pintype "passive+no_connect"))
    )
    (net (code "96") (name "unconnected-(U10-1B2-Pad5)") (class "Default")
      (node (ref "U10") (pin "5") (pinfunction "1B2_5") (pintype "passive+no_connect"))
    )
    (net (code "97") (name "unconnected-(U10-1B3-Pad6)") (class "Default")
      (node (ref "U10") (pin "6") (pinfunction "1B3_6") (pintype "passive+no_connect"))
    )
    (net (code "98") (name "unconnected-(U10-1B4-Pad8)") (class "Default")
      (node (ref "U10") (pin "8") (pinfunction "1B4_8") (pintype "passive+no_connect"))
    )
    (net (code "99") (name "unconnected-(U10-2A2-Pad33)") (class "Default")
      (node (ref "U10") (pin "33") (pinfunction "2A2_33") (pintype "passive+no_connect"))
    )
    (net (code "100") (name "unconnected-(U10-2A3-Pad32)") (class "Default")
      (node (ref "U10") (pin "32") (pinfunction "2A3_32") (pintype "passive+no_connect"))
    )
    (net (code "101") (name "unconnected-(U10-2B2-Pad16)") (class "Default")
      (node (ref "U10") (pin "16") (pinfunction "2B2_16") (pintype "passive+no_connect"))
    )
    (net (code "102") (name "unconnected-(U10-2B3-Pad17)") (class "Default")
      (node (ref "U10") (pin "17") (pinfunction "2B3_17") (pintype "passive+no_connect"))
    )
    (net (code "103") (name "unconnected-(U11-1A2-Pad44)") (class "Default")
      (node (ref "U11") (pin "44") (pinfunction "1A2_44") (pintype "passive+no_connect"))
    )
    (net (code "104") (name "unconnected-(U11-1A3-Pad43)") (class "Default")
      (node (ref "U11") (pin "43") (pinfunction "1A3_43") (pintype "passive+no_connect"))
    )
    (net (code "105") (name "unconnected-(U11-1A4-Pad41)") (class "Default")
      (node (ref "U11") (pin "41") (pinfunction "1A4_41") (pintype "passive+no_connect"))
    )
    (net (code "106") (name "unconnected-(U11-1B2-Pad5)") (class "Default")
      (node (ref "U11") (pin "5") (pinfunction "1B2_5") (pintype "passive+no_connect"))
    )
    (net (code "107") (name "unconnected-(U11-1B3-Pad6)") (class "Default")
      (node (ref "U11") (pin "6") (pinfunction "1B3_6") (pintype "passive+no_connect"))
    )
    (net (code "108") (name "unconnected-(U11-1B4-Pad8)") (class "Default")
      (node (ref "U11") (pin "8") (pinfunction "1B4_8") (pintype "passive+no_connect"))
    )
    (net (code "109") (name "unconnected-(U11-2A6-Pad27)") (class "Default")
      (node (ref "U11") (pin "27") (pinfunction "2A6_27") (pintype "passive+no_connect"))
    )
    (net (code "110") (name "unconnected-(U11-2A7-Pad26)") (class "Default")
      (node (ref "U11") (pin "26") (pinfunction "2A7_26") (pintype "passive+no_connect"))
    )
    (net (code "111") (name "unconnected-(U11-2B6-Pad22)") (class "Default")
      (node (ref "U11") (pin "22") (pinfunction "2B6_22") (pintype "passive+no_connect"))
    )
    (net (code "112") (name "unconnected-(U11-2B7-Pad23)") (class "Default")
      (node (ref "U11") (pin "23") (pinfunction "2B7_23") (pintype "passive+no_connect"))
    )
    (net (code "113") (name "unconnected-(U16-AUX-Pad16)") (class "Default")
      (node (ref "U16") (pin "16") (pinfunction "AUX_16") (pintype "passive+no_connect"))
    )
    (net (code "114") (name "unconnected-(U16-NC-Pad7)") (class "Default")
      (node (ref "U16") (pin "7") (pinfunction "NC_7") (pintype "passive+no_connect"))
    )
    (net (code "115") (name "unconnected-(U16-NC-Pad8)") (class "Default")
      (node (ref "U16") (pin "8") (pinfunction "NC_8") (pintype "passive+no_connect"))
    )
    (net (code "116") (name "unconnected-(U16-NC-Pad9)") (class "Default")
      (node (ref "U16") (pin "9") (pinfunction "NC_9") (pintype "passive+no_connect"))
    )
    (net (code "117") (name "unconnected-(U16-NC-Pad15)") (class "Default")
      (node (ref "U16") (pin "15") (pinfunction "NC_15") (pintype "passive+no_connect"))
    )
  )
)
